# doorbellphat.net
KiCad netlist of a schematic drawn in EAGLE
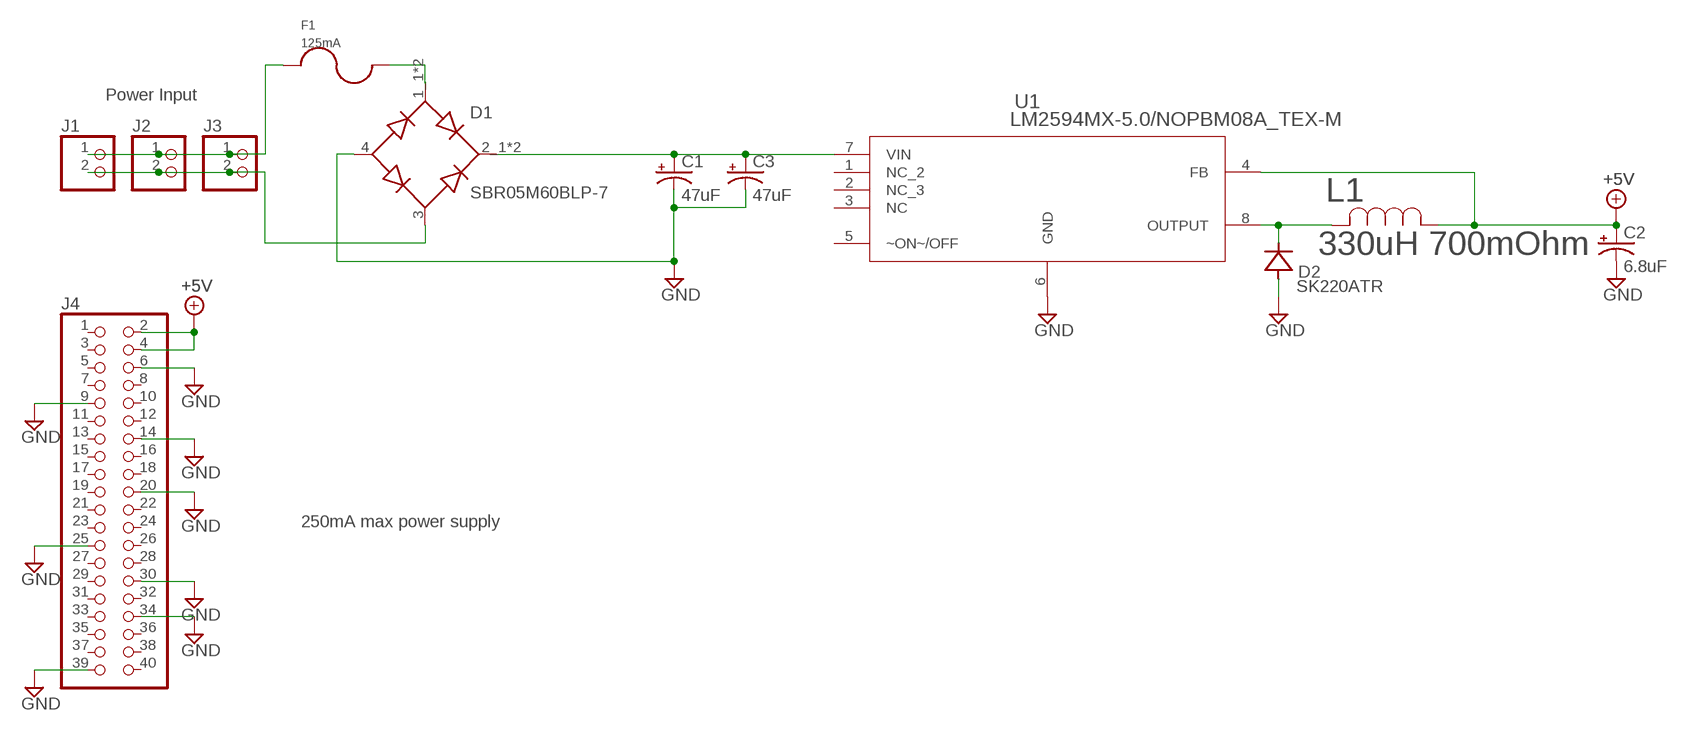
[diagram p0: schematic, sheet 1]

(export (version "E")
  (design (tool "Eeschema 10.0.6"))
  (components
    (comp (ref "C1")
      (value "47uF")
      (footprint "eagle-import:CAPPM7343X310N")
      (fields (field (name "MFR_PART_NO") "TAJD476M035RNJV"))
      (libsource (lib "eagle-import") (part "CPOL-US2917"))
    )
    (comp (ref "C2")
      (value "6.8uF")
      (footprint "eagle-import:2312")
      (fields (field (name "MFR_PART_NO") "293D685X9035C2TE3"))
      (libsource (lib "eagle-import") (part "CPOL-US2312"))
    )
    (comp (ref "C3")
      (value "47uF")
      (footprint "eagle-import:CAPPM7343X310N")
      (fields (field (name "MFR_PART_NO") "TAJD476M035RNJV"))
      (libsource (lib "eagle-import") (part "CPOL-US2917"))
    )
    (comp (ref "D1")
      (value "SBR05M60BLP-7")
      (footprint "eagle-import:RECTIFIER_SBR05M60BLP-7")
      (fields (field (name "DIGI-KEY_PART_NUMBER") "SBR05M60BLPDICT-ND") (field (name "MF") "Diodes Inc."))
      (libsource (lib "eagle-import") (part "SBR05M60BLP-7"))
    )
    (comp (ref "D2")
      (value "SK220ATR")
      (footprint "eagle-import:SMA")
      (libsource (lib "eagle-import") (part "MBRA340T3"))
    )
    (comp (ref "F1")
      (value "125mA")
      (footprint "eagle-import:0603")
      (fields (field (name "MANUFACTURER") "AVX") (field (name "MFR_PART_NO") "F0603G0R10FNTR"))
      (libsource (lib "eagle-import") (part "PICO3"))
    )
    (comp (ref "J1")
      (value "PINHD-1X2")
      (footprint "eagle-import:1X02")
      (libsource (lib "eagle-import") (part "PINHD-1X2"))
    )
    (comp (ref "J2")
      (value "PINHD-1X2")
      (footprint "eagle-import:1X02")
      (libsource (lib "eagle-import") (part "PINHD-1X2"))
    )
    (comp (ref "J3")
      (value "PINHD-1X2")
      (footprint "eagle-import:1X02")
      (libsource (lib "eagle-import") (part "PINHD-1X2"))
    )
    (comp (ref "J4")
      (value "PINHD-2X20")
      (footprint "eagle-import:2X20")
      (libsource (lib "eagle-import") (part "PINHD-2X20"))
    )
    (comp (ref "L1")
      (value "330uH 700mOhm")
      (footprint "eagle-import:IND_BOURNS_SRU1038")
      (fields (field (name "MFR_PART_NO") "SRU1038-331Y"))
      (libsource (lib "eagle-import") (part "SRU1038-331Y"))
    )
    (comp (ref "U1")
      (value "LM2594MX-5.0/NOPBM08A_TEX-M")
      (footprint "eagle-import:M08A_TEX-M")
      (fields (field (name "MANUFACTURER_PART_NUMBER") "LM2594MX-5.0/NOPB"))
      (libsource (lib "eagle-import") (part "LM2594MX-5.0/NOPBM08A_TEX-M"))
    )
  )
  (nets
    (net (code "1") (name "+5V") (class "Default")
      (node (ref "C2") (pin "A") (pinfunction "+_A") (pintype "passive"))
      (node (ref "J4") (pin "2") (pinfunction "2_2") (pintype "passive"))
      (node (ref "J4") (pin "4") (pinfunction "4_4") (pintype "passive"))
      (node (ref "L1") (pin "1") (pinfunction "1_1") (pintype "passive"))
      (node (ref "U1") (pin "4") (pinfunction "FB_4") (pintype "passive"))
    )
    (net (code "2") (name "GND") (class "Default")
      (node (ref "C1") (pin "C") (pinfunction "-_C") (pintype "passive"))
      (node (ref "C2") (pin "C") (pinfunction "-_C") (pintype "passive"))
      (node (ref "C3") (pin "C") (pinfunction "-_C") (pintype "passive"))
      (node (ref "D1") (pin "4") (pinfunction "-_4") (pintype "passive"))
      (node (ref "D2") (pin "A") (pinfunction "A_A") (pintype "passive"))
      (node (ref "J4") (pin "14") (pinfunction "14_14") (pintype "passive"))
      (node (ref "J4") (pin "20") (pinfunction "20_20") (pintype "passive"))
      (node (ref "J4") (pin "25") (pinfunction "25_25") (pintype "passive"))
      (node (ref "J4") (pin "30") (pinfunction "30_30") (pintype "passive"))
      (node (ref "J4") (pin "34") (pinfunction "34_34") (pintype "passive"))
      (node (ref "J4") (pin "39") (pinfunction "39_39") (pintype "passive"))
      (node (ref "J4") (pin "6") (pinfunction "6_6") (pintype "passive"))
      (node (ref "J4") (pin "9") (pinfunction "9_9") (pintype "passive"))
      (node (ref "U1") (pin "6") (pinfunction "GND_6") (pintype "passive"))
    )
    (net (code "3") (name "Net-(C1-+)") (class "Default")
      (node (ref "C1") (pin "A") (pinfunction "+_A") (pintype "passive"))
      (node (ref "C3") (pin "A") (pinfunction "+_A") (pintype "passive"))
      (node (ref "D1") (pin "2_1") (pinfunction "+_2_1") (pintype "passive"))
      (node (ref "D1") (pin "2_2") (pinfunction "+_2_2") (pintype "passive"))
      (node (ref "U1") (pin "7") (pinfunction "VIN_7") (pintype "input"))
    )
    (net (code "4") (name "Net-(D1-AC2)") (class "Default")
      (node (ref "D1") (pin "3") (pinfunction "AC2_3") (pintype "passive"))
      (node (ref "J1") (pin "2") (pinfunction "2_2") (pintype "passive"))
      (node (ref "J2") (pin "2") (pinfunction "2_2") (pintype "passive"))
      (node (ref "J3") (pin "2") (pinfunction "2_2") (pintype "passive"))
    )
    (net (code "5") (name "Net-(F1-1)") (class "Default")
      (node (ref "D1") (pin "1_1") (pinfunction "AC1_1_1") (pintype "passive"))
      (node (ref "D1") (pin "1_2") (pinfunction "AC1_1_2") (pintype "passive"))
      (node (ref "F1") (pin "2") (pinfunction "1_2") (pintype "bidirectional"))
    )
    (net (code "6") (name "Net-(F1-2)") (class "Default")
      (node (ref "F1") (pin "1") (pinfunction "2_1") (pintype "bidirectional"))
      (node (ref "J1") (pin "1") (pinfunction "1_1") (pintype "passive"))
      (node (ref "J2") (pin "1") (pinfunction "1_1") (pintype "passive"))
      (node (ref "J3") (pin "1") (pinfunction "1_1") (pintype "passive"))
    )
    (net (code "7") (name "Net-(U1-OUTPUT)") (class "Default")
      (node (ref "D2") (pin "C") (pinfunction "C_C") (pintype "passive"))
      (node (ref "L1") (pin "2") (pinfunction "2_2") (pintype "passive"))
      (node (ref "U1") (pin "8") (pinfunction "OUTPUT_8") (pintype "output"))
    )
    (net (code "8") (name "unconnected-(J4-Pad1)") (class "Default")
      (node (ref "J4") (pin "1") (pinfunction "1_1") (pintype "passive"))
    )
    (net (code "9") (name "unconnected-(J4-Pad3)") (class "Default")
      (node (ref "J4") (pin "3") (pinfunction "3_3") (pintype "passive"))
    )
    (net (code "10") (name "unconnected-(J4-Pad5)") (class "Default")
      (node (ref "J4") (pin "5") (pinfunction "5_5") (pintype "passive"))
    )
    (net (code "11") (name "unconnected-(J4-Pad7)") (class "Default")
      (node (ref "J4") (pin "7") (pinfunction "7_7") (pintype "passive"))
    )
    (net (code "12") (name "unconnected-(J4-Pad8)") (class "Default")
      (node (ref "J4") (pin "8") (pinfunction "8_8") (pintype "passive"))
    )
    (net (code "13") (name "unconnected-(J4-Pad10)") (class "Default")
      (node (ref "J4") (pin "10") (pinfunction "10_10") (pintype "passive"))
    )
    (net (code "14") (name "unconnected-(J4-Pad11)") (class "Default")
      (node (ref "J4") (pin "11") (pinfunction "11_11") (pintype "passive"))
    )
    (net (code "15") (name "unconnected-(J4-Pad12)") (class "Default")
      (node (ref "J4") (pin "12") (pinfunction "12_12") (pintype "passive"))
    )
    (net (code "16") (name "unconnected-(J4-Pad13)") (class "Default")
      (node (ref "J4") (pin "13") (pinfunction "13_13") (pintype "passive"))
    )
    (net (code "17") (name "unconnected-(J4-Pad15)") (class "Default")
      (node (ref "J4") (pin "15") (pinfunction "15_15") (pintype "passive"))
    )
    (net (code "18") (name "unconnected-(J4-Pad16)") (class "Default")
      (node (ref "J4") (pin "16") (pinfunction "16_16") (pintype "passive"))
    )
    (net (code "19") (name "unconnected-(J4-Pad17)") (class "Default")
      (node (ref "J4") (pin "17") (pinfunction "17_17") (pintype "passive"))
    )
    (net (code "20") (name "unconnected-(J4-Pad18)") (class "Default")
      (node (ref "J4") (pin "18") (pinfunction "18_18") (pintype "passive"))
    )
    (net (code "21") (name "unconnected-(J4-Pad19)") (class "Default")
      (node (ref "J4") (pin "19") (pinfunction "19_19") (pintype "passive"))
    )
    (net (code "22") (name "unconnected-(J4-Pad21)") (class "Default")
      (node (ref "J4") (pin "21") (pinfunction "21_21") (pintype "passive"))
    )
    (net (code "23") (name "unconnected-(J4-Pad22)") (class "Default")
      (node (ref "J4") (pin "22") (pinfunction "22_22") (pintype "passive"))
    )
    (net (code "24") (name "unconnected-(J4-Pad23)") (class "Default")
      (node (ref "J4") (pin "23") (pinfunction "23_23") (pintype "passive"))
    )
    (net (code "25") (name "unconnected-(J4-Pad24)") (class "Default")
      (node (ref "J4") (pin "24") (pinfunction "24_24") (pintype "passive"))
    )
    (net (code "26") (name "unconnected-(J4-Pad26)") (class "Default")
      (node (ref "J4") (pin "26") (pinfunction "26_26") (pintype "passive"))
    )
    (net (code "27") (name "unconnected-(J4-Pad27)") (class "Default")
      (node (ref "J4") (pin "27") (pinfunction "27_27") (pintype "passive"))
    )
    (net (code "28") (name "unconnected-(J4-Pad28)") (class "Default")
      (node (ref "J4") (pin "28") (pinfunction "28_28") (pintype "passive"))
    )
    (net (code "29") (name "unconnected-(J4-Pad29)") (class "Default")
      (node (ref "J4") (pin "29") (pinfunction "29_29") (pintype "passive"))
    )
    (net (code "30") (name "unconnected-(J4-Pad31)") (class "Default")
      (node (ref "J4") (pin "31") (pinfunction "31_31") (pintype "passive"))
    )
    (net (code "31") (name "unconnected-(J4-Pad32)") (class "Default")
      (node (ref "J4") (pin "32") (pinfunction "32_32") (pintype "passive"))
    )
    (net (code "32") (name "unconnected-(J4-Pad33)") (class "Default")
      (node (ref "J4") (pin "33") (pinfunction "33_33") (pintype "passive"))
    )
    (net (code "33") (name "unconnected-(J4-Pad35)") (class "Default")
      (node (ref "J4") (pin "35") (pinfunction "35_35") (pintype "passive"))
    )
    (net (code "34") (name "unconnected-(J4-Pad36)") (class "Default")
      (node (ref "J4") (pin "36") (pinfunction "36_36") (pintype "passive"))
    )
    (net (code "35") (name "unconnected-(J4-Pad37)") (class "Default")
      (node (ref "J4") (pin "37") (pinfunction "37_37") (pintype "passive"))
    )
    (net (code "36") (name "unconnected-(J4-Pad38)") (class "Default")
      (node (ref "J4") (pin "38") (pinfunction "38_38") (pintype "passive"))
    )
    (net (code "37") (name "unconnected-(J4-Pad40)") (class "Default")
      (node (ref "J4") (pin "40") (pinfunction "40_40") (pintype "passive"))
    )
    (net (code "38") (name "unconnected-(U1-NC-Pad3)") (class "Default")
      (node (ref "U1") (pin "3") (pinfunction "NC_3") (pintype "passive"))
    )
    (net (code "39") (name "unconnected-(U1-NC_2-Pad1)") (class "Default")
      (node (ref "U1") (pin "1") (pinfunction "NC_2_1") (pintype "passive"))
    )
    (net (code "40") (name "unconnected-(U1-NC_3-Pad2)") (class "Default")
      (node (ref "U1") (pin "2") (pinfunction "NC_3_2") (pintype "passive"))
    )
    (net (code "41") (name "unconnected-(U1-~{ON}{slash}OFF-Pad5)") (class "Default")
      (node (ref "U1") (pin "5") (pinfunction "~{ON}/OFF_5") (pintype "passive"))
    )
  )
)
